# Power_Board.net
KiCad netlist of a schematic drawn in EAGLE
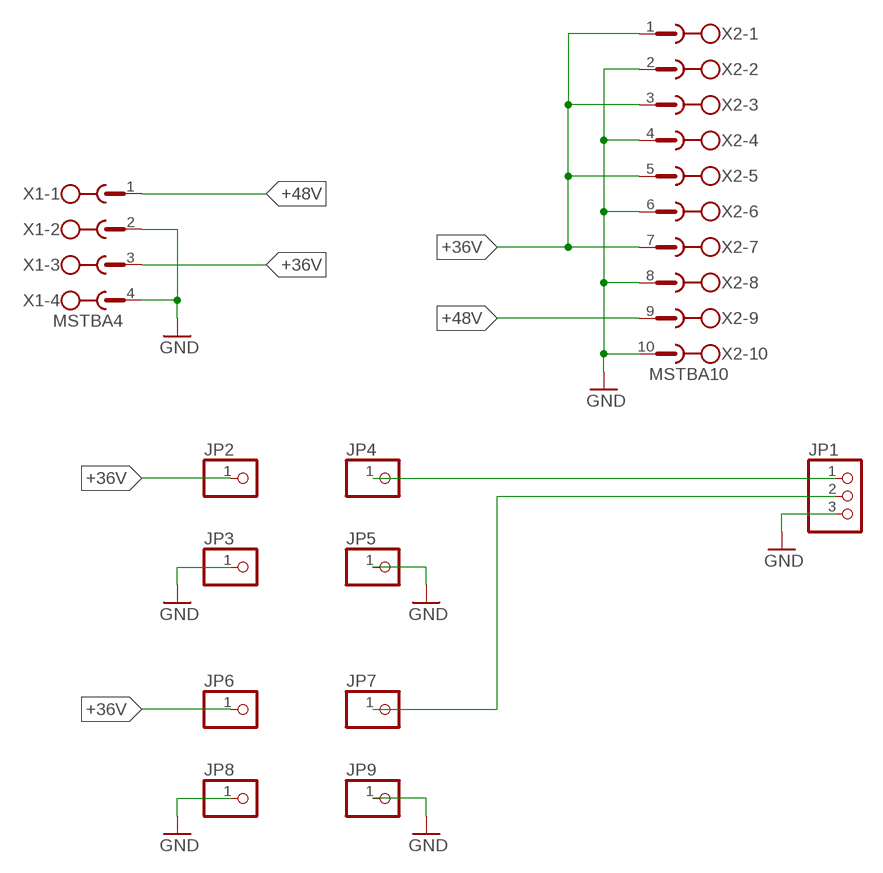
[diagram p0: schematic, sheet 1]

(export (version "E")
  (design (tool "Eeschema 10.0.6"))
  (components
    (comp (ref "JP1")
      (value "PINHD-1X3/90")
      (footprint "eagle-import:1X03_90")
      (libsource (lib "eagle-import") (part "PINHD-1X3/90"))
    )
    (comp (ref "JP2")
      (value "PINHD-1X1")
      (footprint "eagle-import:1X01")
      (libsource (lib "eagle-import") (part "PINHD-1X1"))
    )
    (comp (ref "JP3")
      (value "PINHD-1X1")
      (footprint "eagle-import:1X01")
      (libsource (lib "eagle-import") (part "PINHD-1X1"))
    )
    (comp (ref "JP4")
      (value "PINHD-1X1")
      (footprint "eagle-import:1X01")
      (libsource (lib "eagle-import") (part "PINHD-1X1"))
    )
    (comp (ref "JP5")
      (value "PINHD-1X1")
      (footprint "eagle-import:1X01")
      (libsource (lib "eagle-import") (part "PINHD-1X1"))
    )
    (comp (ref "JP6")
      (value "PINHD-1X1")
      (footprint "eagle-import:1X01")
      (libsource (lib "eagle-import") (part "PINHD-1X1"))
    )
    (comp (ref "JP7")
      (value "PINHD-1X1")
      (footprint "eagle-import:1X01")
      (libsource (lib "eagle-import") (part "PINHD-1X1"))
    )
    (comp (ref "JP8")
      (value "PINHD-1X1")
      (footprint "eagle-import:1X01")
      (libsource (lib "eagle-import") (part "PINHD-1X1"))
    )
    (comp (ref "JP9")
      (value "PINHD-1X1")
      (footprint "eagle-import:1X01")
      (libsource (lib "eagle-import") (part "PINHD-1X1"))
    )
    (comp (ref "X1")
      (value "MSTBA4")
      (footprint "eagle-import:MSTBA4")
      (libsource (lib "eagle-import") (part "MSTBA4"))
    )
    (comp (ref "X2")
      (value "MSTBA10")
      (footprint "eagle-import:MSTBA10")
      (libsource (lib "eagle-import") (part "MSTBA10"))
    )
  )
  (nets
    (net (code "1") (name "+36V") (class "Default")
      (node (ref "JP2") (pin "1") (pinfunction "1_1") (pintype "passive"))
      (node (ref "JP6") (pin "1") (pinfunction "1_1") (pintype "passive"))
      (node (ref "X1") (pin "3") (pinfunction "1_3") (pintype "passive"))
      (node (ref "X2") (pin "1") (pinfunction "1_1") (pintype "passive"))
      (node (ref "X2") (pin "3") (pinfunction "1_3") (pintype "passive"))
      (node (ref "X2") (pin "5") (pinfunction "1_5") (pintype "passive"))
      (node (ref "X2") (pin "7") (pinfunction "1_7") (pintype "passive"))
    )
    (net (code "2") (name "+48V") (class "Default")
      (node (ref "X1") (pin "1") (pinfunction "1_1") (pintype "passive"))
      (node (ref "X2") (pin "9") (pinfunction "1_9") (pintype "passive"))
    )
    (net (code "3") (name "GND") (class "Default")
      (node (ref "JP1") (pin "3") (pinfunction "3_3") (pintype "passive"))
      (node (ref "JP3") (pin "1") (pinfunction "1_1") (pintype "passive"))
      (node (ref "JP5") (pin "1") (pinfunction "1_1") (pintype "passive"))
      (node (ref "JP8") (pin "1") (pinfunction "1_1") (pintype "passive"))
      (node (ref "JP9") (pin "1") (pinfunction "1_1") (pintype "passive"))
      (node (ref "X1") (pin "2") (pinfunction "1_2") (pintype "passive"))
      (node (ref "X1") (pin "4") (pinfunction "1_4") (pintype "passive"))
      (node (ref "X2") (pin "10") (pinfunction "1_10") (pintype "passive"))
      (node (ref "X2") (pin "2") (pinfunction "1_2") (pintype "passive"))
      (node (ref "X2") (pin "4") (pinfunction "1_4") (pintype "passive"))
      (node (ref "X2") (pin "6") (pinfunction "1_6") (pintype "passive"))
      (node (ref "X2") (pin "8") (pinfunction "1_8") (pintype "passive"))
    )
    (net (code "4") (name "Net-(JP1-Pad1)") (class "Default")
      (node (ref "JP1") (pin "1") (pinfunction "1_1") (pintype "passive"))
      (node (ref "JP4") (pin "1") (pinfunction "1_1") (pintype "passive"))
    )
    (net (code "5") (name "Net-(JP1-Pad2)") (class "Default")
      (node (ref "JP1") (pin "2") (pinfunction "2_2") (pintype "passive"))
      (node (ref "JP7") (pin "1") (pinfunction "1_1") (pintype "passive"))
    )
  )
)
